# Breakout_Board.net
KiCad netlist of a schematic drawn in Altium Designer
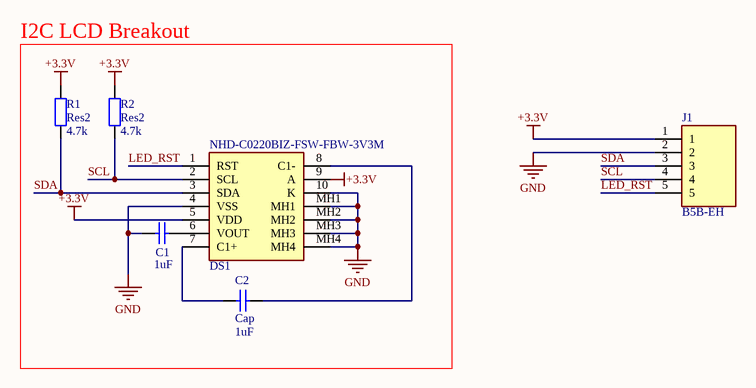
[diagram p0: Breakout_Board.SchDoc]

(export (version "E")
  (design (tool "Eeschema 10.0.6"))
  (components
    (comp (ref "C1")
      (value "1uF")
      (footprint "C0805")
      (description "Capacitor")
      (fields (field (name "Comment") "Cap") (field (name "PUBLISHER") "Altium Limited"))
      (libsource (lib "Miscellaneous Devices") (part "Cap"))
    )
    (comp (ref "C2")
      (value "Cap")
      (footprint "C0805")
      (description "Capacitor")
      (fields (field (name "ALTIUM_VALUE") "1uF") (field (name "PUBLISHER") "Altium Limited"))
      (libsource (lib "Miscellaneous Devices") (part "Cap"))
    )
    (comp (ref "DS1")
      (value "NHD-C0220BIZ-FSW-FBW-3V3M")
      (footprint "Embedded:NHDC0220BIZFSWFBW3V3M")
      (description "Display")
      (fields (field (name "MOUSER PART NUMBER") "763-C0220BIZ-FSW-FBW"))
      (libsource (lib "*") (part "NHD-C0220BIZ-FSW-FBW-3V3M"))
    )
    (comp (ref "J1")
      (value "B5B-EH")
      (footprint "Embedded:SHDR5W64P0X250_1X5_1500X380X600P")
      (description "Connector")
      (libsource (lib "*") (part "B5B-EH"))
    )
    (comp (ref "R1")
      (value "Res2")
      (footprint "C0805")
      (description "Resistor")
      (fields (field (name "ALTIUM_VALUE") "4.7k") (field (name "PUBLISHER") "Altium Limited"))
      (libsource (lib "Miscellaneous Devices") (part "Res2"))
    )
    (comp (ref "R2")
      (value "Res2")
      (footprint "C0805")
      (description "Resistor")
      (fields (field (name "ALTIUM_VALUE") "4.7k") (field (name "PUBLISHER") "Altium Limited"))
      (libsource (lib "Miscellaneous Devices") (part "Res2"))
    )
  )
  (nets
    (net (code "1") (name "+3.3V") (class "Default")
      (node (ref "DS1") (pin "5") (pinfunction "VDD_5") (pintype "passive"))
      (node (ref "DS1") (pin "9") (pinfunction "A_9") (pintype "passive"))
      (node (ref "J1") (pin "1") (pinfunction "1_1") (pintype "passive"))
      (node (ref "R1") (pin "2") (pinfunction "2_2") (pintype "passive"))
      (node (ref "R2") (pin "2") (pinfunction "2_2") (pintype "passive"))
    )
    (net (code "2") (name "/LED_RST") (class "Default")
      (node (ref "DS1") (pin "1") (pinfunction "RST_1") (pintype "passive"))
      (node (ref "J1") (pin "5") (pinfunction "5_5") (pintype "passive"))
    )
    (net (code "3") (name "/SCL") (class "Default")
      (node (ref "DS1") (pin "2") (pinfunction "SCL_2") (pintype "passive"))
      (node (ref "J1") (pin "4") (pinfunction "4_4") (pintype "passive"))
      (node (ref "R2") (pin "1") (pinfunction "1_1") (pintype "passive"))
    )
    (net (code "4") (name "/SDA") (class "Default")
      (node (ref "DS1") (pin "3") (pinfunction "SDA_3") (pintype "passive"))
      (node (ref "J1") (pin "3") (pinfunction "3_3") (pintype "passive"))
      (node (ref "R1") (pin "1") (pinfunction "1_1") (pintype "passive"))
    )
    (net (code "5") (name "GND") (class "Default")
      (node (ref "C1") (pin "1") (pinfunction "1_1") (pintype "passive"))
      (node (ref "DS1") (pin "10") (pinfunction "K_10") (pintype "passive"))
      (node (ref "DS1") (pin "4") (pinfunction "VSS_4") (pintype "passive"))
      (node (ref "DS1") (pin "MH1") (pinfunction "MH1_MH1") (pintype "passive"))
      (node (ref "DS1") (pin "MH2") (pinfunction "MH2_MH2") (pintype "passive"))
      (node (ref "DS1") (pin "MH3") (pinfunction "MH3_MH3") (pintype "passive"))
      (node (ref "DS1") (pin "MH4") (pinfunction "MH4_MH4") (pintype "passive"))
      (node (ref "J1") (pin "2") (pinfunction "2_2") (pintype "passive"))
    )
    (net (code "6") (name "Net-(DS1-C1+)") (class "Default")
      (node (ref "C2") (pin "1") (pinfunction "1_1") (pintype "passive"))
      (node (ref "DS1") (pin "7") (pinfunction "C1+_7") (pintype "passive"))
    )
    (net (code "7") (name "Net-(DS1-C1-)") (class "Default")
      (node (ref "C2") (pin "2") (pinfunction "2_2") (pintype "passive"))
      (node (ref "DS1") (pin "8") (pinfunction "C1-_8") (pintype "passive"))
    )
    (net (code "8") (name "Net-(DS1-VOUT)") (class "Default")
      (node (ref "C1") (pin "2") (pinfunction "2_2") (pintype "passive"))
      (node (ref "DS1") (pin "6") (pinfunction "VOUT_6") (pintype "passive"))
    )
  )
)
